# Sensors.net
KiCad netlist of a schematic drawn in Altium Designer
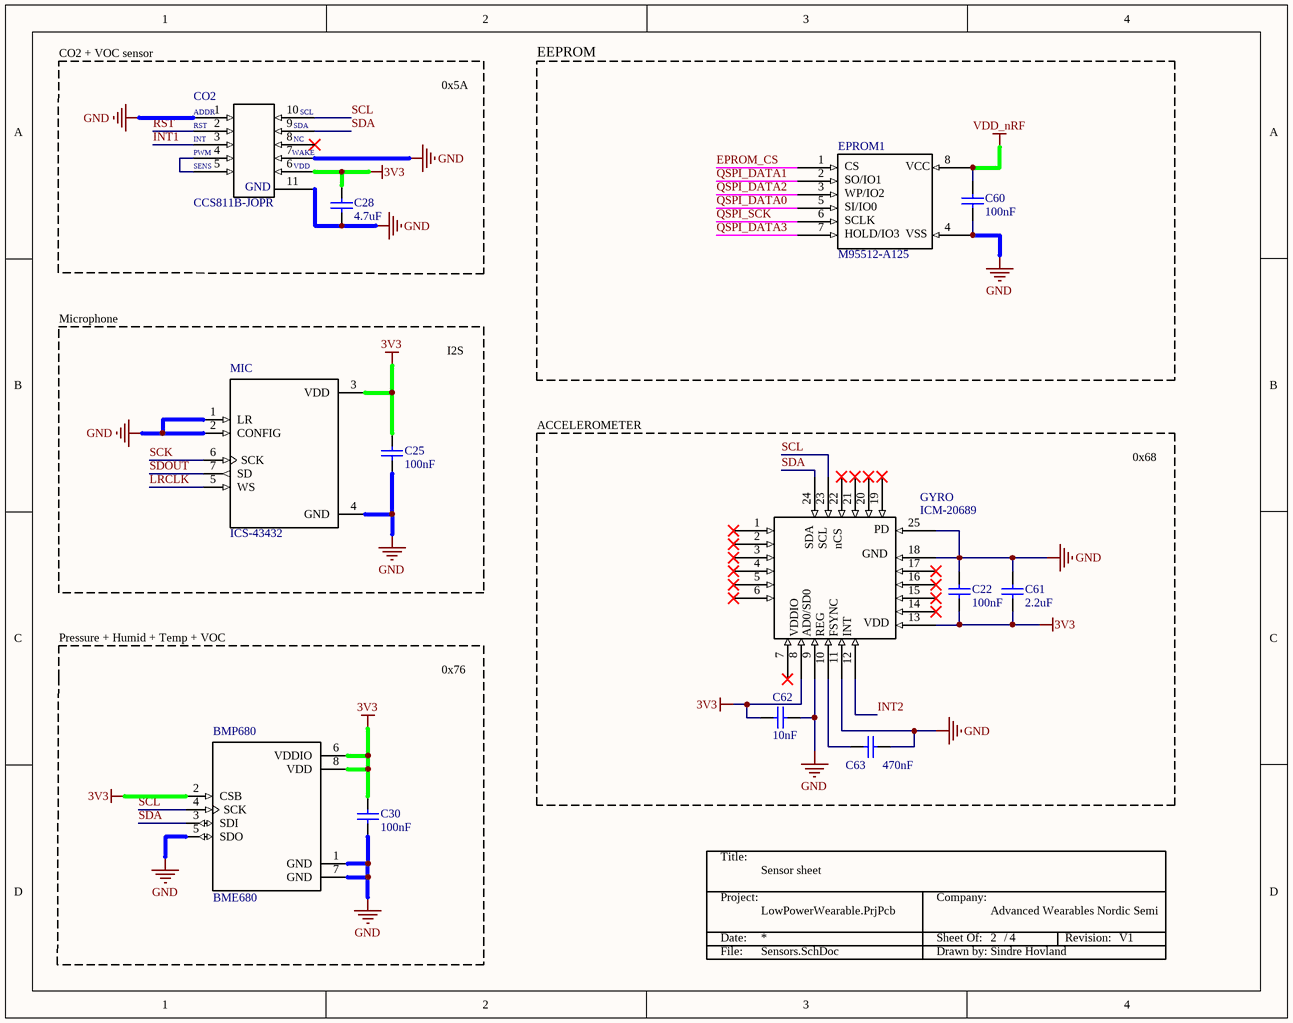
[diagram p0: Sensors.SchDoc]

(export (version "E")
  (design (tool "Eeschema 10.0.6"))
  (components
    (comp (ref "BMP680")
      (value "BME680")
      (footprint "bme680 ic")
      (description "Gas, Humidity, Pressure, Temperature Sensor IÂ²C, SPI Output")
      (fields (field (name "DIGI-KEY_PART_NUMBER") "828-1077-1-ND") (field (name "MF") "Bosch Sensortec"))
      (libsource (lib "MCU") (part "BME680"))
    )
    (comp (ref "C22")
      (value "100nF")
      (footprint "C0402")
      (description "Capacitor")
      (fields (field (name "PUBLISHER") "Altium Limited"))
      (libsource (lib "NeuronV4") (part "CAP"))
    )
    (comp (ref "C25")
      (value "100nF")
      (footprint "C0402")
      (description "Capacitor")
      (fields (field (name "PUBLISHER") "Altium Limited"))
      (libsource (lib "NeuronV4") (part "CAP"))
    )
    (comp (ref "C28")
      (value "4.7uF")
      (footprint "C0402")
      (description "Capacitor")
      (fields (field (name "PUBLISHER") "Altium Limited"))
      (libsource (lib "NeuronV4") (part "CAP"))
    )
    (comp (ref "C30")
      (value "100nF")
      (footprint "C0402")
      (description "Capacitor")
      (fields (field (name "PUBLISHER") "Altium Limited"))
      (libsource (lib "NeuronV4") (part "CAP"))
    )
    (comp (ref "C60")
      (value "100nF")
      (footprint "C0402")
      (description "Capacitor")
      (fields (field (name "PUBLISHER") "Altium Limited"))
      (libsource (lib "NeuronV4") (part "CAP"))
    )
    (comp (ref "C61")
      (value "2.2uF")
      (footprint "C0402")
      (description "Capacitor")
      (fields (field (name "PUBLISHER") "Altium Limited"))
      (libsource (lib "NeuronV4") (part "CAP"))
    )
    (comp (ref "C62")
      (value "10nF")
      (footprint "C0402")
      (description "Capacitor")
      (fields (field (name "PUBLISHER") "Altium Limited"))
      (libsource (lib "NeuronV4") (part "CAP"))
    )
    (comp (ref "C63")
      (value "470nF")
      (footprint "C0402")
      (description "Capacitor")
      (fields (field (name "PUBLISHER") "Altium Limited"))
      (libsource (lib "NeuronV4") (part "CAP"))
    )
    (comp (ref "CO2")
      (value "CCS811B-JOPR")
      (footprint "ccs811")
      (description "CO2 and VOC sensor")
      (fields (field (name "MANUFACTURER PART NUMBER") "CCS811"))
      (libsource (lib "NeuronV4") (part "CCS811"))
    )
    (comp (ref "EPROM1")
      (value "M95512-A125")
      (footprint "M95512-A125")
      (description "EPROM M95512-A125 512K")
      (libsource (lib "NeuronV4") (part "Flash SPI"))
    )
    (comp (ref "GYRO")
      (value "ICM-20689")
      (footprint "QFN50P400X400X90_HS-25N")
      (description "ICM-20689 6 aksis gyro")
      (libsource (lib "NeuronV4") (part "ICM-20689"))
    )
    (comp (ref "MIC")
      (value "ICS-43432")
      (footprint "MIC_ICS-43432")
      (fields (field (name "MF") "TDK InvenSense"))
      (libsource (lib "NeuronV4") (part "ICS-43432"))
    )
  )
  (nets
    (net (code "1") (name "/EPROM_CS") (class "Default") (node (ref "EPROM1") (pin "1") (pintype "input")))
    (net (code "2") (name "/INT1") (class "Default") (node (ref "CO2") (pin "3") (pintype "input")))
    (net (code "3") (name "/INT2") (class "Default") (node (ref "GYRO") (pin "12") (pintype "input")))
    (net (code "4") (name "/LRCLK") (class "Default")
      (node (ref "MIC") (pin "5") (pinfunction "WS_5") (pintype "input"))
    )
    (net (code "5") (name "/QSPI_DATA0") (class "Default") (node (ref "EPROM1") (pin "5") (pintype "input")))
    (net (code "6") (name "/QSPI_DATA1") (class "Default") (node (ref "EPROM1") (pin "2") (pintype "input")))
    (net (code "7") (name "/QSPI_DATA2") (class "Default") (node (ref "EPROM1") (pin "3") (pintype "input")))
    (net (code "8") (name "/QSPI_DATA3") (class "Default") (node (ref "EPROM1") (pin "7") (pintype "input")))
    (net (code "9") (name "/QSPI_SCK") (class "Default") (node (ref "EPROM1") (pin "6") (pintype "input")))
    (net (code "10") (name "/RST") (class "Default") (node (ref "CO2") (pin "2") (pintype "input")))
    (net (code "11") (name "/SCK") (class "Default")
      (node (ref "MIC") (pin "6") (pinfunction "SCK_6") (pintype "input"))
    )
    (net (code "12") (name "/SCL") (class "Default")
      (node (ref "BMP680") (pin "4") (pinfunction "SCK_4") (pintype "input"))
      (node (ref "CO2") (pin "10") (pintype "input"))
      (node (ref "GYRO") (pin "23") (pintype "input"))
    )
    (net (code "13") (name "/SDA") (class "Default")
      (node (ref "BMP680") (pin "3") (pinfunction "SDI_3") (pintype "bidirectional"))
      (node (ref "CO2") (pin "9") (pintype "input"))
      (node (ref "GYRO") (pin "24") (pintype "input"))
    )
    (net (code "14") (name "/SDOUT") (class "Default")
      (node (ref "MIC") (pin "7") (pinfunction "SD_7") (pintype "output"))
    )
    (net (code "15") (name "3V3") (class "Default")
      (node (ref "BMP680") (pin "2") (pinfunction "CSB_2") (pintype "input"))
      (node (ref "BMP680") (pin "6") (pinfunction "VDDIO_6") (pintype "power_in"))
      (node (ref "BMP680") (pin "8") (pinfunction "VDD_8") (pintype "power_in"))
      (node (ref "C22") (pin "1") (pinfunction "1_1") (pintype "passive"))
      (node (ref "C25") (pin "2") (pinfunction "2_2") (pintype "passive"))
      (node (ref "C28") (pin "2") (pinfunction "2_2") (pintype "passive"))
      (node (ref "C30") (pin "1") (pinfunction "1_1") (pintype "passive"))
      (node (ref "C61") (pin "1") (pinfunction "1_1") (pintype "passive"))
      (node (ref "C62") (pin "2") (pinfunction "2_2") (pintype "passive"))
      (node (ref "CO2") (pin "6") (pintype "input"))
      (node (ref "GYRO") (pin "13") (pintype "input"))
      (node (ref "GYRO") (pin "8") (pintype "input"))
      (node (ref "MIC") (pin "3") (pinfunction "VDD_3") (pintype "power_in"))
    )
    (net (code "16") (name "GND") (class "Default")
      (node (ref "BMP680") (pin "1") (pinfunction "GND_1") (pintype "power_in"))
      (node (ref "BMP680") (pin "5") (pinfunction "SDO_5") (pintype "bidirectional"))
      (node (ref "BMP680") (pin "7") (pinfunction "GND_7") (pintype "power_in"))
      (node (ref "C22") (pin "2") (pinfunction "2_2") (pintype "passive"))
      (node (ref "C25") (pin "1") (pinfunction "1_1") (pintype "passive"))
      (node (ref "C28") (pin "1") (pinfunction "1_1") (pintype "passive"))
      (node (ref "C30") (pin "2") (pinfunction "2_2") (pintype "passive"))
      (node (ref "C60") (pin "1") (pinfunction "1_1") (pintype "passive"))
      (node (ref "C61") (pin "2") (pinfunction "2_2") (pintype "passive"))
      (node (ref "C62") (pin "1") (pinfunction "1_1") (pintype "passive"))
      (node (ref "C63") (pin "2") (pinfunction "2_2") (pintype "passive"))
      (node (ref "CO2") (pin "1") (pintype "input"))
      (node (ref "CO2") (pin "11") (pinfunction "11_11") (pintype "passive"))
      (node (ref "CO2") (pin "7") (pintype "input"))
      (node (ref "EPROM1") (pin "4") (pintype "input"))
      (node (ref "GYRO") (pin "11") (pintype "input"))
      (node (ref "GYRO") (pin "18") (pintype "input"))
      (node (ref "GYRO") (pin "25") (pintype "input"))
      (node (ref "GYRO") (pin "9") (pintype "input"))
      (node (ref "MIC") (pin "1") (pinfunction "LR_1") (pintype "input"))
      (node (ref "MIC") (pin "2") (pinfunction "CONFIG_2") (pintype "input"))
      (node (ref "MIC") (pin "4") (pinfunction "GND_4") (pintype "power_in"))
    )
    (net (code "17") (name "Net-(C63-Pad1)") (class "Default")
      (node (ref "C63") (pin "1") (pinfunction "1_1") (pintype "passive"))
      (node (ref "GYRO") (pin "10") (pintype "input"))
    )
    (net (code "18") (name "Net-(CO2-Pad4)") (class "Default")
      (node (ref "CO2") (pin "4") (pintype "input"))
      (node (ref "CO2") (pin "5") (pintype "input"))
    )
    (net (code "19") (name "VDD_nRF") (class "Default")
      (node (ref "C60") (pin "2") (pinfunction "2_2") (pintype "passive"))
      (node (ref "EPROM1") (pin "8") (pintype "input"))
    )
    (net (code "20") (name "unconnected-(CO2-Pad8)") (class "Default")
      (node (ref "CO2") (pin "8") (pintype "input+no_connect"))
    )
    (net (code "21") (name "unconnected-(GYRO-Pad1)") (class "Default")
      (node (ref "GYRO") (pin "1") (pintype "input+no_connect"))
    )
    (net (code "22") (name "unconnected-(GYRO-Pad2)") (class "Default")
      (node (ref "GYRO") (pin "2") (pintype "input+no_connect"))
    )
    (net (code "23") (name "unconnected-(GYRO-Pad3)") (class "Default")
      (node (ref "GYRO") (pin "3") (pintype "input+no_connect"))
    )
    (net (code "24") (name "unconnected-(GYRO-Pad4)") (class "Default")
      (node (ref "GYRO") (pin "4") (pintype "input+no_connect"))
    )
    (net (code "25") (name "unconnected-(GYRO-Pad5)") (class "Default")
      (node (ref "GYRO") (pin "5") (pintype "input+no_connect"))
    )
    (net (code "26") (name "unconnected-(GYRO-Pad6)") (class "Default")
      (node (ref "GYRO") (pin "6") (pintype "input+no_connect"))
    )
    (net (code "27") (name "unconnected-(GYRO-Pad7)") (class "Default")
      (node (ref "GYRO") (pin "7") (pintype "input+no_connect"))
    )
    (net (code "28") (name "unconnected-(GYRO-Pad14)") (class "Default")
      (node (ref "GYRO") (pin "14") (pintype "input+no_connect"))
    )
    (net (code "29") (name "unconnected-(GYRO-Pad15)") (class "Default")
      (node (ref "GYRO") (pin "15") (pintype "input+no_connect"))
    )
    (net (code "30") (name "unconnected-(GYRO-Pad16)") (class "Default")
      (node (ref "GYRO") (pin "16") (pintype "input+no_connect"))
    )
    (net (code "31") (name "unconnected-(GYRO-Pad17)") (class "Default")
      (node (ref "GYRO") (pin "17") (pintype "input+no_connect"))
    )
    (net (code "32") (name "unconnected-(GYRO-Pad19)") (class "Default")
      (node (ref "GYRO") (pin "19") (pintype "input+no_connect"))
    )
    (net (code "33") (name "unconnected-(GYRO-Pad20)") (class "Default")
      (node (ref "GYRO") (pin "20") (pintype "input+no_connect"))
    )
    (net (code "34") (name "unconnected-(GYRO-Pad21)") (class "Default")
      (node (ref "GYRO") (pin "21") (pintype "input+no_connect"))
    )
    (net (code "35") (name "unconnected-(GYRO-Pad22)") (class "Default")
      (node (ref "GYRO") (pin "22") (pintype "input+no_connect"))
    )
  )
)
